# DS163-1_0-B.net
KiCad netlist of a schematic drawn in Altium Designer
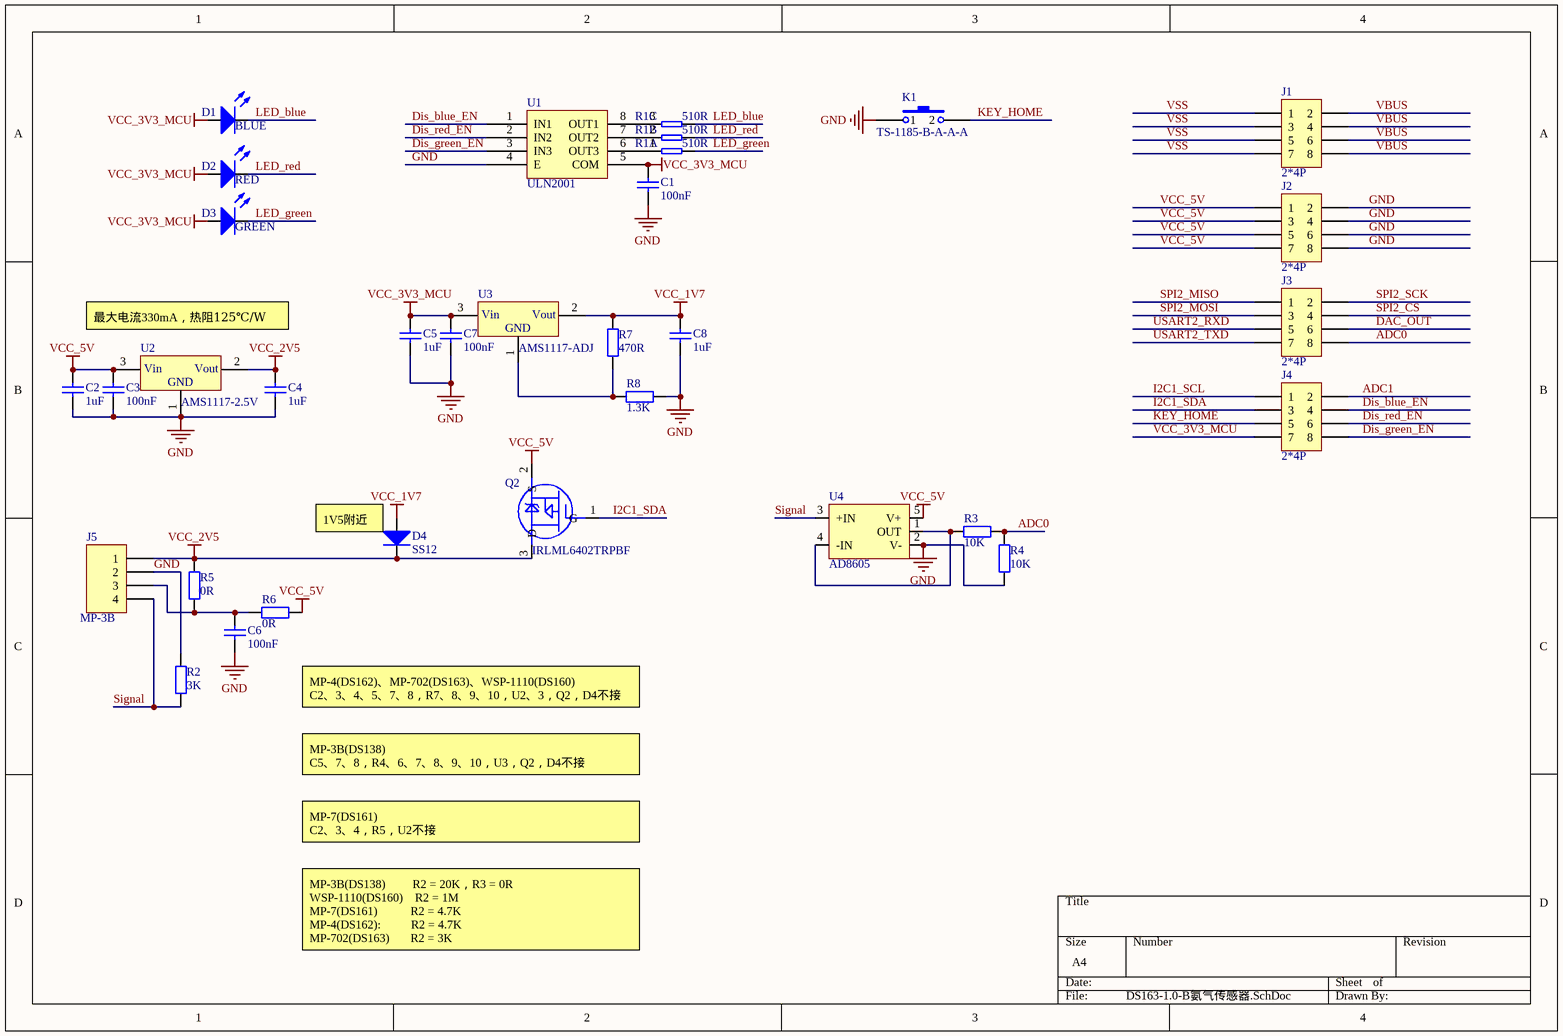
[diagram p0: DS163-1.0-B氨气传感器.SchDoc]

(export (version "E")
  (design (tool "Eeschema 10.0.6"))
  (components
    (comp (ref "C1")
      (value "100nF")
      (footprint "0603CAP")
      (description "贴片电容")
      (fields (field (name "Comment") "SMDCAP00013"))
      (libsource (lib "AD_SCH") (part "MLCC 100nF 50V ±10％ 0603"))
    )
    (comp (ref "C2")
      (value "1uF")
      (footprint "0603CAP")
      (description "贴片电容")
      (fields (field (name "Comment") "SMDCAP00015"))
      (libsource (lib "AD_SCH") (part "MLCC 1uF 50V ±10％ 0603"))
    )
    (comp (ref "C3")
      (value "100nF")
      (footprint "0603CAP")
      (description "贴片电容")
      (fields (field (name "Comment") "SMDCAP00013"))
      (libsource (lib "AD_SCH") (part "MLCC 100nF 50V ±10％ 0603"))
    )
    (comp (ref "C4")
      (value "1uF")
      (footprint "0603CAP")
      (description "贴片电容")
      (fields (field (name "Comment") "SMDCAP00015"))
      (libsource (lib "AD_SCH") (part "MLCC 1uF 50V ±10％ 0603"))
    )
    (comp (ref "C5")
      (value "1uF")
      (footprint "0603CAP")
      (description "贴片电容")
      (fields (field (name "Comment") "SMDCAP00015"))
      (libsource (lib "AD_SCH") (part "MLCC 1uF 50V ±10％ 0603"))
    )
    (comp (ref "C6")
      (value "100nF")
      (footprint "0603CAP")
      (description "贴片电容")
      (fields (field (name "Comment") "SMDCAP00013"))
      (libsource (lib "AD_SCH") (part "MLCC 100nF 50V ±10％ 0603"))
    )
    (comp (ref "C7")
      (value "100nF")
      (footprint "0603CAP")
      (description "贴片电容")
      (fields (field (name "Comment") "SMDCAP00013"))
      (libsource (lib "AD_SCH") (part "MLCC 100nF 50V ±10％ 0603"))
    )
    (comp (ref "C8")
      (value "1uF")
      (footprint "0603CAP")
      (description "贴片电容")
      (fields (field (name "Comment") "SMDCAP00015"))
      (libsource (lib "AD_SCH") (part "MLCC 1uF 50V ±10％ 0603"))
    )
    (comp (ref "D1")
      (value "BLUE")
      (footprint "LED_0805")
      (description "贴片LED")
      (fields (field (name "Comment") "SMDLED00010"))
      (libsource (lib "AD_SCH") (part "Chip 蓝色LED 0805"))
    )
    (comp (ref "D2")
      (value "RED")
      (footprint "LED_0805")
      (description "贴片LED")
      (fields (field (name "Comment") "SMDLED00003"))
      (libsource (lib "AD_SCH") (part "Chip 红色LED 0805"))
    )
    (comp (ref "D3")
      (value "GREEN")
      (footprint "LED_0805")
      (description "贴片LED")
      (fields (field (name "Comment") "Chip 翠绿LED 0805"))
      (libsource (lib "AD_SCH") (part "Chip 翠绿LED 0805"))
    )
    (comp (ref "D4")
      (value "SS12")
      (footprint "SMA/DO-214AC")
      (description "贴片肖特基二极管")
      (fields (field (name "Comment") "SMDDIODE06003"))
      (libsource (lib "AD_SCH") (part "SS12 SMA/DO-214AC（1N5817）"))
    )
    (comp (ref "J1")
      (value "2*4P")
      (footprint "X1321WVS-2x04J-C40D53")
      (description "双排针2x4P 立贴 1.27mm")
      (fields (field (name "Comment") "X1321WVS-2x04J-C40D53"))
      (libsource (lib "AD_SCH") (part "X1321WVS-2x04J-C40D53"))
    )
    (comp (ref "J2")
      (value "2*4P")
      (footprint "X1321WVS-2x04J-C40D53")
      (description "双排针2x4P 立贴 1.27mm")
      (fields (field (name "Comment") "X1321WVS-2x04J-C40D53"))
      (libsource (lib "AD_SCH") (part "X1321WVS-2x04J-C40D53"))
    )
    (comp (ref "J3")
      (value "2*4P")
      (footprint "X1321WVS-2x04J-C40D53")
      (description "双排针2x4P 立贴 1.27mm")
      (fields (field (name "Comment") "X1321WVS-2x04J-C40D53"))
      (libsource (lib "AD_SCH") (part "X1321WVS-2x04J-C40D53"))
    )
    (comp (ref "J4")
      (value "2*4P")
      (footprint "X1321WVS-2x04J-C40D53")
      (description "双排针2x4P 立贴 1.27mm")
      (fields (field (name "Comment") "X1321WVS-2x04J-C40D53"))
      (libsource (lib "AD_SCH") (part "X1321WVS-2x04J-C40D53"))
    )
    (comp (ref "J5")
      (value "MP-3B")
      (footprint "SIP4")
      (fields (field (name "Comment") "SL000000042"))
      (libsource (lib "AD_SCH") (part "DIP4 单排直针 间距2.54mm 针长11mm 铜"))
    )
    (comp (ref "K1")
      (value "TS-1185-B-A-A-A")
      (footprint "KEY_TS-1185-x-A-A-A")
      (description "轻触开关")
      (libsource (lib "AD_SCH") (part "TS-1185-B-A-A-A"))
    )
    (comp (ref "Q2")
      (value "IRLML6402TRPBF")
      (footprint "SOT23")
      (description "贴片P-MOS管")
      (fields (field (name "Comment") "SMDPMOS00001"))
      (libsource (lib "AD_SCH") (part "IRLML6402TRPBF SOT-23 IR"))
    )
    (comp (ref "R1")
      (value "510R")
      (footprint "0603RES_Pack4")
      (description "贴片排阻")
      (fields (field (name "Comment") "SMDRES05003"))
      (libsource (lib "AD_SCH") (part "Chip R*4 510R 1/16W ±5％ 0603"))
    )
    (comp (ref "R2")
      (value "3K")
      (footprint "0603RES")
      (description "贴片电阻")
      (fields (field (name "Comment") "Chip 3K 1/16W ±1％ 0603"))
      (libsource (lib "AD_SCH") (part "Chip 3K 1/16W ±1％ 0603"))
    )
    (comp (ref "R3")
      (value "10K")
      (footprint "0603RES")
      (description "贴片电阻")
      (fields (field (name "Comment") "SMDRES00056"))
      (libsource (lib "") (part "Chip 10K 1/16W ±1％ 0603_1"))
    )
    (comp (ref "R4")
      (value "10K")
      (footprint "0603RES")
      (description "贴片电阻")
      (fields (field (name "Comment") "SMDRES00056"))
      (libsource (lib "AD_SCH") (part "Chip 10K 1/16W ±1％ 0603"))
    )
    (comp (ref "R5")
      (value "0R")
      (footprint "0603RES")
      (description "贴片电阻")
      (fields (field (name "Comment") "Chip 0R 1/16W ±1％ 0603"))
      (libsource (lib "AD_SCH") (part "Chip 0R 1/16W ±1％ 0603"))
    )
    (comp (ref "R6")
      (value "0R")
      (footprint "0603RES")
      (description "贴片电阻")
      (fields (field (name "Comment") "Chip 0R 1/16W ±1％ 0603"))
      (libsource (lib "") (part "Chip 0R 1/16W ±1％ 0603_1"))
    )
    (comp (ref "R7")
      (value "470R")
      (footprint "0603RES")
      (description "贴片电阻")
      (fields (field (name "Comment") "SMDRES00027"))
      (libsource (lib "AD_SCH") (part "Chip 470R 1/16W ±1％ 0603"))
    )
    (comp (ref "R8")
      (value "1.3K")
      (footprint "0603RES")
      (description "贴片电阻")
      (fields (field (name "Comment") "SMDRES00038"))
      (libsource (lib "AD_SCH") (part "Chip 1.3K 1/16W ±1％ 0603"))
    )
    (comp (ref "U1")
      (value "ULN2001")
      (footprint "SO-8")
      (description "电机驱动芯片")
      (fields (field (name "Comment") "SMDIC000018"))
      (libsource (lib "AD_SCH") (part "ULN2001 SOP-8"))
    )
    (comp (ref "U2")
      (value "AMS1117-2.5V")
      (footprint "SOT223")
      (description "稳压芯片")
      (fields (field (name "Comment") "SMDIC000020"))
      (libsource (lib "AD_SCH") (part "AMS1117-3.3V SOT-223"))
    )
    (comp (ref "U3")
      (value "AMS1117-ADJ")
      (footprint "SOT223")
      (description "稳压芯片")
      (fields (field (name "Comment") "SMDIC000020"))
      (libsource (lib "AD_SCH") (part "AMS1117-3.3V SOT-223"))
    )
    (comp (ref "U4")
      (value "AD8605")
      (footprint "SOT23-5")
      (description "运放芯片")
      (libsource (lib "AD_SCH") (part "AD8605 SOT23-5"))
    )
  )
  (nets
    (net (code "1") (name "/ADC0") (class "Default")
      (node (ref "J3") (pin "8") (pinfunction "8_8") (pintype "passive"))
      (node (ref "R3") (pin "1") (pinfunction "1_1") (pintype "passive"))
      (node (ref "R4") (pin "1") (pinfunction "1_1") (pintype "passive"))
    )
    (net (code "2") (name "/ADC1") (class "Default")
      (node (ref "J4") (pin "2") (pinfunction "2_2") (pintype "passive"))
    )
    (net (code "3") (name "/DAC_OUT") (class "Default")
      (node (ref "J3") (pin "6") (pinfunction "6_6") (pintype "passive"))
    )
    (net (code "4") (name "/Dis_blue_EN") (class "Default")
      (node (ref "J4") (pin "4") (pinfunction "4_4") (pintype "passive"))
      (node (ref "U1") (pin "1") (pinfunction "IN1_1") (pintype "passive"))
    )
    (net (code "5") (name "/Dis_green_EN") (class "Default")
      (node (ref "J4") (pin "8") (pinfunction "8_8") (pintype "passive"))
      (node (ref "U1") (pin "3") (pinfunction "IN3_3") (pintype "passive"))
    )
    (net (code "6") (name "/Dis_red_EN") (class "Default")
      (node (ref "J4") (pin "6") (pinfunction "6_6") (pintype "passive"))
      (node (ref "U1") (pin "2") (pinfunction "IN2_2") (pintype "passive"))
    )
    (net (code "7") (name "/I2C1_SCL") (class "Default")
      (node (ref "J4") (pin "1") (pinfunction "1_1") (pintype "passive"))
    )
    (net (code "8") (name "/I2C1_SDA") (class "Default")
      (node (ref "J4") (pin "3") (pinfunction "3_3") (pintype "passive"))
      (node (ref "Q2") (pin "1") (pinfunction "G_1") (pintype "passive"))
    )
    (net (code "9") (name "/KEY_HOME") (class "Default")
      (node (ref "J4") (pin "5") (pinfunction "5_5") (pintype "passive"))
      (node (ref "K1") (pin "2") (pinfunction "2_2") (pintype "passive"))
    )
    (net (code "10") (name "/LED_blue") (class "Default")
      (node (ref "D1") (pin "2") (pinfunction "K_2") (pintype "passive"))
      (node (ref "R1") (pin "6") (pinfunction "6_6") (pintype "passive"))
    )
    (net (code "11") (name "/LED_green") (class "Default")
      (node (ref "D3") (pin "2") (pinfunction "K_2") (pintype "passive"))
      (node (ref "R1") (pin "8") (pinfunction "8_8") (pintype "passive"))
    )
    (net (code "12") (name "/LED_red") (class "Default")
      (node (ref "D2") (pin "2") (pinfunction "K_2") (pintype "passive"))
      (node (ref "R1") (pin "7") (pinfunction "7_7") (pintype "passive"))
    )
    (net (code "13") (name "/SPI2_CS") (class "Default")
      (node (ref "J3") (pin "4") (pinfunction "4_4") (pintype "passive"))
    )
    (net (code "14") (name "/SPI2_MISO") (class "Default")
      (node (ref "J3") (pin "1") (pinfunction "1_1") (pintype "passive"))
    )
    (net (code "15") (name "/SPI2_MOSI") (class "Default")
      (node (ref "J3") (pin "3") (pinfunction "3_3") (pintype "passive"))
    )
    (net (code "16") (name "/SPI2_SCK") (class "Default")
      (node (ref "J3") (pin "2") (pinfunction "2_2") (pintype "passive"))
    )
    (net (code "17") (name "/Signal") (class "Default")
      (node (ref "J5") (pin "4") (pinfunction "4_4") (pintype "passive"))
      (node (ref "R2") (pin "2") (pinfunction "2_2") (pintype "passive"))
      (node (ref "U4") (pin "3") (pinfunction "+IN_3") (pintype "passive"))
    )
    (net (code "18") (name "/USART2_RXD") (class "Default")
      (node (ref "J3") (pin "5") (pinfunction "5_5") (pintype "passive"))
    )
    (net (code "19") (name "/USART2_TXD") (class "Default")
      (node (ref "J3") (pin "7") (pinfunction "7_7") (pintype "passive"))
    )
    (net (code "20") (name "/VBUS") (class "Default")
      (node (ref "J1") (pin "2") (pinfunction "2_2") (pintype "passive"))
      (node (ref "J1") (pin "4") (pinfunction "4_4") (pintype "passive"))
      (node (ref "J1") (pin "6") (pinfunction "6_6") (pintype "passive"))
      (node (ref "J1") (pin "8") (pinfunction "8_8") (pintype "passive"))
    )
    (net (code "21") (name "/VSS") (class "Default")
      (node (ref "J1") (pin "1") (pinfunction "1_1") (pintype "passive"))
      (node (ref "J1") (pin "3") (pinfunction "3_3") (pintype "passive"))
      (node (ref "J1") (pin "5") (pinfunction "5_5") (pintype "passive"))
      (node (ref "J1") (pin "7") (pinfunction "7_7") (pintype "passive"))
    )
    (net (code "22") (name "GND") (class "Default")
      (node (ref "C1") (pin "1") (pinfunction "1_1") (pintype "passive"))
      (node (ref "C2") (pin "1") (pinfunction "1_1") (pintype "passive"))
      (node (ref "C3") (pin "1") (pinfunction "1_1") (pintype "passive"))
      (node (ref "C4") (pin "1") (pinfunction "1_1") (pintype "passive"))
      (node (ref "C5") (pin "1") (pinfunction "1_1") (pintype "passive"))
      (node (ref "C6") (pin "1") (pinfunction "1_1") (pintype "passive"))
      (node (ref "C7") (pin "1") (pinfunction "1_1") (pintype "passive"))
      (node (ref "C8") (pin "1") (pinfunction "1_1") (pintype "passive"))
      (node (ref "J2") (pin "2") (pinfunction "2_2") (pintype "passive"))
      (node (ref "J2") (pin "4") (pinfunction "4_4") (pintype "passive"))
      (node (ref "J2") (pin "6") (pinfunction "6_6") (pintype "passive"))
      (node (ref "J2") (pin "8") (pinfunction "8_8") (pintype "passive"))
      (node (ref "J5") (pin "2") (pinfunction "2_2") (pintype "passive"))
      (node (ref "K1") (pin "1") (pinfunction "1_1") (pintype "passive"))
      (node (ref "R2") (pin "1") (pinfunction "1_1") (pintype "passive"))
      (node (ref "R4") (pin "2") (pinfunction "2_2") (pintype "passive"))
      (node (ref "R8") (pin "2") (pinfunction "2_2") (pintype "passive"))
      (node (ref "U1") (pin "4") (pinfunction "E_4") (pintype "passive"))
      (node (ref "U2") (pin "1") (pinfunction "GND_1") (pintype "passive"))
      (node (ref "U4") (pin "2") (pinfunction "V-_2") (pintype "passive"))
    )
    (net (code "23") (name "Net-(C6-Pad2)") (class "Default")
      (node (ref "C6") (pin "2") (pinfunction "2_2") (pintype "passive"))
      (node (ref "J5") (pin "3") (pinfunction "3_3") (pintype "passive"))
      (node (ref "R5") (pin "1") (pinfunction "1_1") (pintype "passive"))
      (node (ref "R6") (pin "2") (pinfunction "2_2") (pintype "passive"))
    )
    (net (code "24") (name "Net-(U1-OUT1)") (class "Default")
      (node (ref "R1") (pin "3") (pinfunction "3_3") (pintype "passive"))
      (node (ref "U1") (pin "8") (pinfunction "OUT1_8") (pintype "passive"))
    )
    (net (code "25") (name "Net-(U1-OUT2)") (class "Default")
      (node (ref "R1") (pin "2") (pinfunction "2_2") (pintype "passive"))
      (node (ref "U1") (pin "7") (pinfunction "OUT2_7") (pintype "passive"))
    )
    (net (code "26") (name "Net-(U1-OUT3)") (class "Default")
      (node (ref "R1") (pin "1") (pinfunction "1_1") (pintype "passive"))
      (node (ref "U1") (pin "6") (pinfunction "OUT3_6") (pintype "passive"))
    )
    (net (code "27") (name "Net-(U3-GND)") (class "Default")
      (node (ref "R7") (pin "1") (pinfunction "1_1") (pintype "passive"))
      (node (ref "R8") (pin "1") (pinfunction "1_1") (pintype "passive"))
      (node (ref "U3") (pin "1") (pinfunction "GND_1") (pintype "passive"))
    )
    (net (code "28") (name "Net-(U4--IN)") (class "Default")
      (node (ref "R3") (pin "2") (pinfunction "2_2") (pintype "passive"))
      (node (ref "U4") (pin "1") (pinfunction "OUT_1") (pintype "passive"))
      (node (ref "U4") (pin "4") (pinfunction "-IN_4") (pintype "passive"))
    )
    (net (code "29") (name "VCC_1V7") (class "Default")
      (node (ref "C8") (pin "2") (pinfunction "2_2") (pintype "passive"))
      (node (ref "D4") (pin "1") (pinfunction "A_1") (pintype "passive"))
      (node (ref "R7") (pin "2") (pinfunction "2_2") (pintype "passive"))
      (node (ref "U3") (pin "2") (pinfunction "Vout_2") (pintype "passive"))
    )
    (net (code "30") (name "VCC_2V5") (class "Default")
      (node (ref "C4") (pin "2") (pinfunction "2_2") (pintype "passive"))
      (node (ref "D4") (pin "2") (pinfunction "K_2") (pintype "passive"))
      (node (ref "J5") (pin "1") (pinfunction "1_1") (pintype "passive"))
      (node (ref "Q2") (pin "3") (pinfunction "D_3") (pintype "passive"))
      (node (ref "R5") (pin "2") (pinfunction "2_2") (pintype "passive"))
      (node (ref "U2") (pin "2") (pinfunction "Vout_2") (pintype "passive"))
    )
    (net (code "31") (name "VCC_3V3_MCU") (class "Default")
      (node (ref "C1") (pin "2") (pinfunction "2_2") (pintype "passive"))
      (node (ref "C5") (pin "2") (pinfunction "2_2") (pintype "passive"))
      (node (ref "C7") (pin "2") (pinfunction "2_2") (pintype "passive"))
      (node (ref "D1") (pin "1") (pinfunction "A_1") (pintype "passive"))
      (node (ref "D2") (pin "1") (pinfunction "A_1") (pintype "passive"))
      (node (ref "D3") (pin "1") (pinfunction "A_1") (pintype "passive"))
      (node (ref "J4") (pin "7") (pinfunction "7_7") (pintype "passive"))
      (node (ref "U1") (pin "5") (pinfunction "COM_5") (pintype "passive"))
      (node (ref "U3") (pin "3") (pinfunction "Vin_3") (pintype "passive"))
    )
    (net (code "32") (name "VCC_5V") (class "Default")
      (node (ref "C2") (pin "2") (pinfunction "2_2") (pintype "passive"))
      (node (ref "C3") (pin "2") (pinfunction "2_2") (pintype "passive"))
      (node (ref "J2") (pin "1") (pinfunction "1_1") (pintype "passive"))
      (node (ref "J2") (pin "3") (pinfunction "3_3") (pintype "passive"))
      (node (ref "J2") (pin "5") (pinfunction "5_5") (pintype "passive"))
      (node (ref "J2") (pin "7") (pinfunction "7_7") (pintype "passive"))
      (node (ref "Q2") (pin "2") (pinfunction "S_2") (pintype "passive"))
      (node (ref "R6") (pin "1") (pinfunction "1_1") (pintype "passive"))
      (node (ref "U2") (pin "3") (pinfunction "Vin_3") (pintype "passive"))
      (node (ref "U4") (pin "5") (pinfunction "V+_5") (pintype "passive"))
    )
  )
)
